# cytron_dip.net
KiCad netlist of a schematic drawn in EAGLE
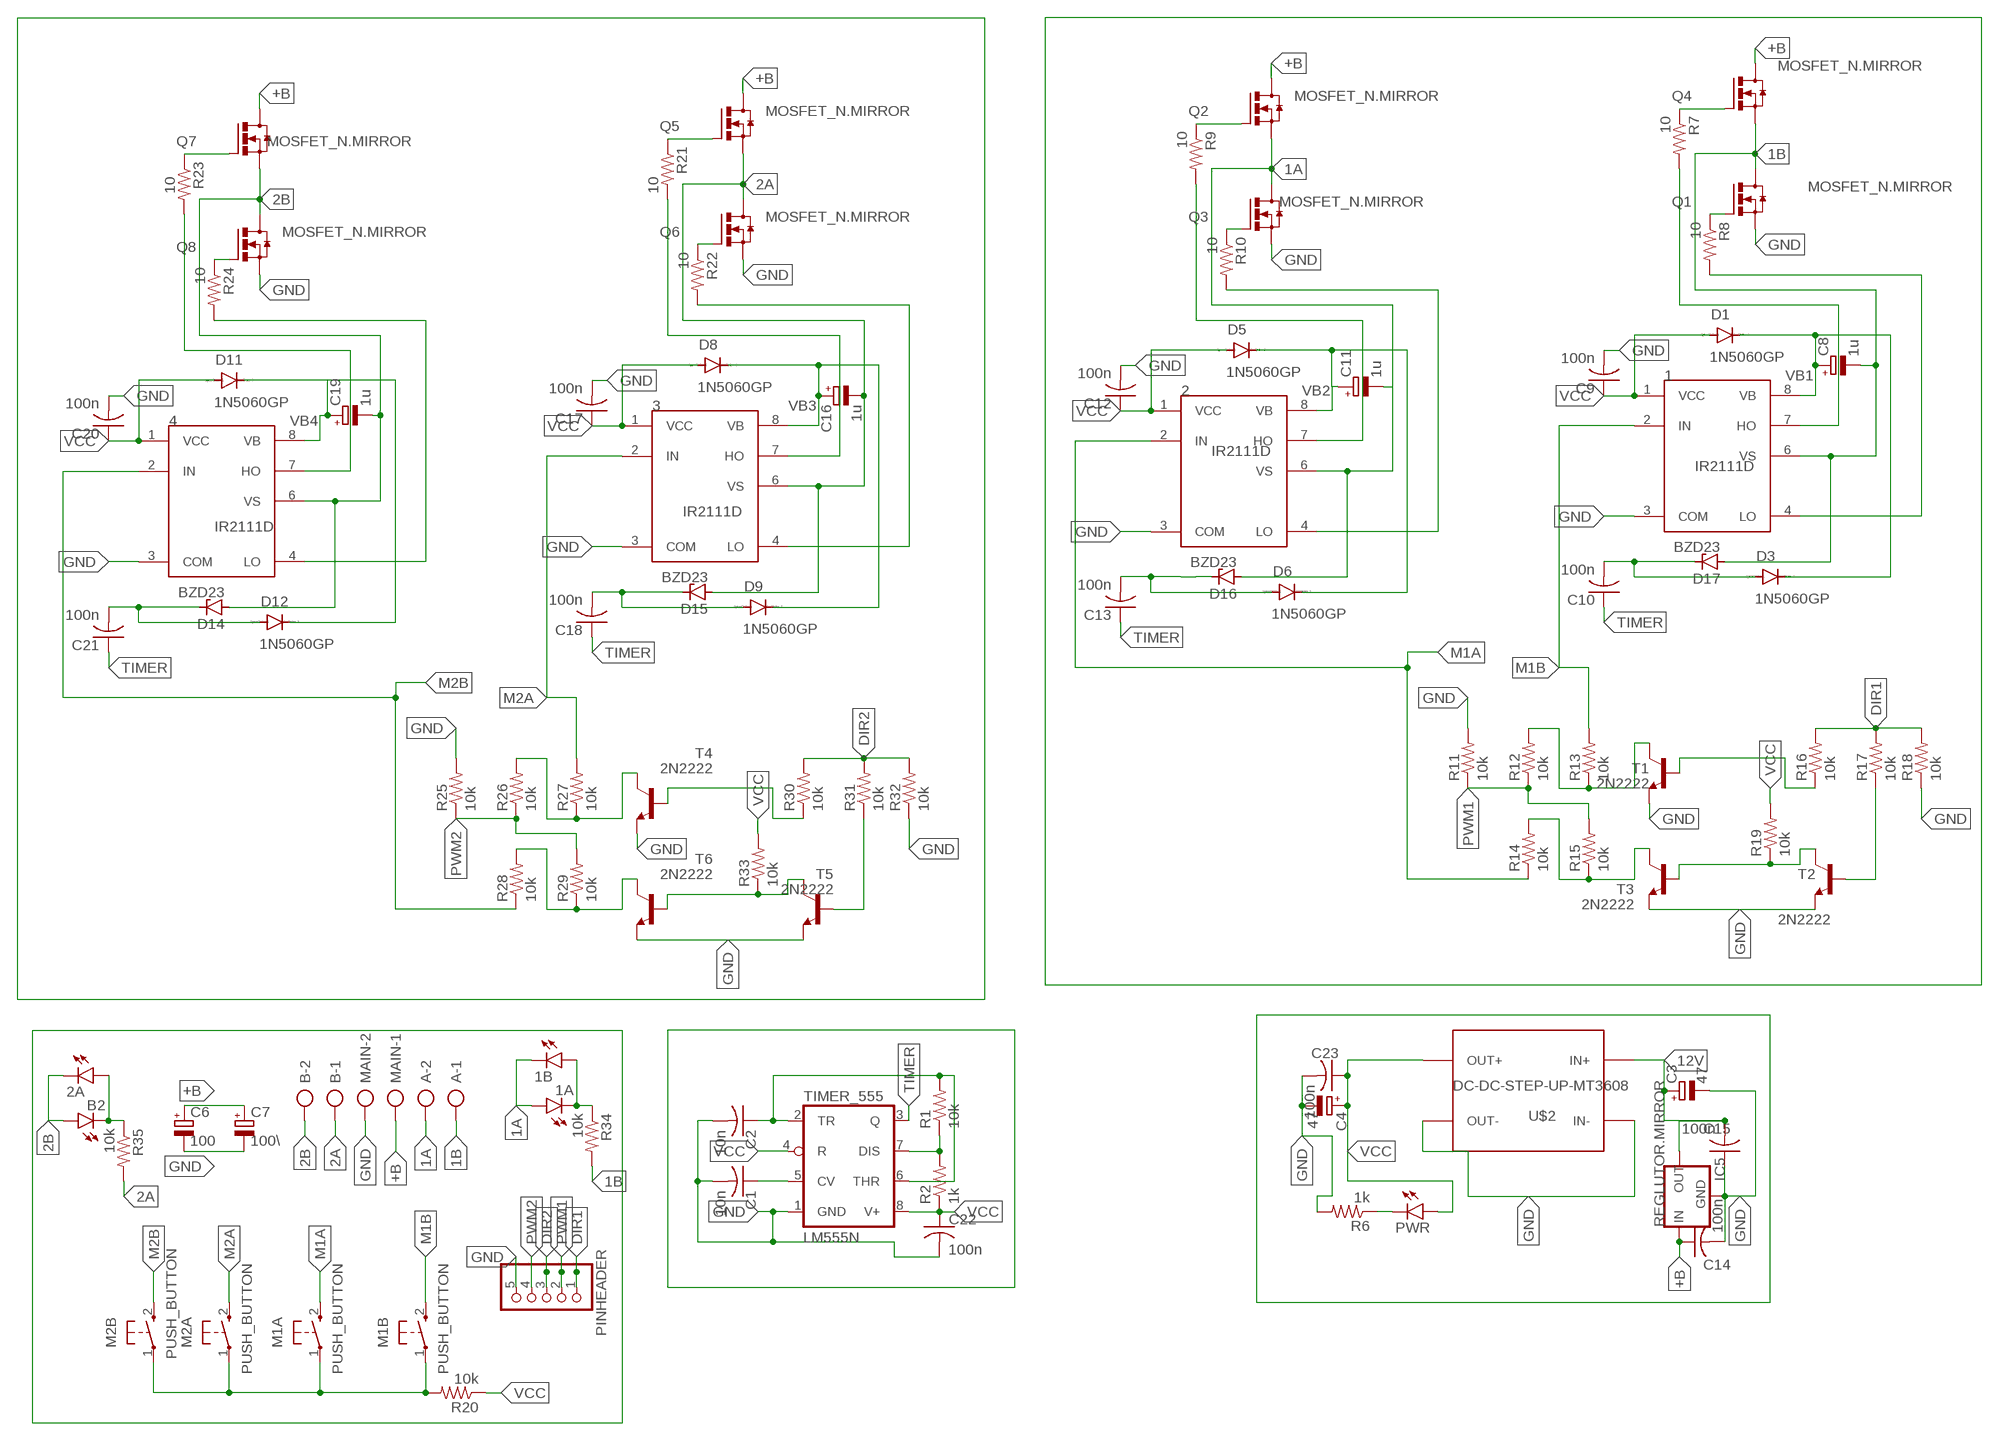
[diagram p0: schematic, sheet 1]

(export (version "E")
  (design (tool "Eeschema 10.0.6"))
  (components
    (comp (ref "1")
      (value "IR2111D")
      (footprint "eagle-import:DIL08")
      (libsource (lib "eagle-import") (part "IR2111D"))
    )
    (comp (ref "1A")
      (value "LED3MM")
      (footprint "eagle-import:LED3MM")
      (libsource (lib "eagle-import") (part "LED3MM"))
    )
    (comp (ref "1B")
      (value "LED3MM")
      (footprint "eagle-import:LED3MM")
      (libsource (lib "eagle-import") (part "LED3MM"))
    )
    (comp (ref "2")
      (value "IR2111D")
      (footprint "eagle-import:DIL08")
      (libsource (lib "eagle-import") (part "IR2111D"))
    )
    (comp (ref "2A")
      (value "LED3MM")
      (footprint "eagle-import:LED3MM")
      (libsource (lib "eagle-import") (part "LED3MM"))
    )
    (comp (ref "3")
      (value "IR2111D")
      (footprint "eagle-import:DIL08")
      (libsource (lib "eagle-import") (part "IR2111D"))
    )
    (comp (ref "4")
      (value "IR2111D")
      (footprint "eagle-import:DIL08")
      (libsource (lib "eagle-import") (part "IR2111D"))
    )
    (comp (ref "A")
      (value "AK300/22")
      (footprint "eagle-import:XTALRR488W60L1090T465H350B")
      (libsource (lib "eagle-import") (part "AK300/22"))
    )
    (comp (ref "B")
      (value "AK300/22")
      (footprint "eagle-import:XTALRR488W60L1090T465H350B")
      (libsource (lib "eagle-import") (part "AK300/22"))
    )
    (comp (ref "B2")
      (value "LED3MM")
      (footprint "eagle-import:LED3MM")
      (libsource (lib "eagle-import") (part "LED3MM"))
    )
    (comp (ref "C1")
      (value "10n")
      (footprint "eagle-import:C025-025X050")
      (libsource (lib "eagle-import") (part "C-US025-025X050"))
    )
    (comp (ref "C2")
      (value "10n")
      (footprint "eagle-import:C025-025X050")
      (libsource (lib "eagle-import") (part "C-US025-025X050"))
    )
    (comp (ref "C3")
      (value "47")
      (footprint "eagle-import:E5-10,5")
      (libsource (lib "eagle-import") (part "CPOL-EUE5-10.5"))
    )
    (comp (ref "C4")
      (value "47")
      (footprint "eagle-import:E5-10,5")
      (libsource (lib "eagle-import") (part "CPOL-EUE5-10.5"))
    )
    (comp (ref "C6")
      (value "100")
      (footprint "eagle-import:E5-10,5")
      (libsource (lib "eagle-import") (part "CPOL-EUE5-10.5"))
    )
    (comp (ref "C7")
      (value "100\\")
      (footprint "eagle-import:E5-10,5")
      (libsource (lib "eagle-import") (part "CPOL-EUE5-10.5"))
    )
    (comp (ref "C8")
      (value "1u")
      (footprint "eagle-import:E5-5")
      (libsource (lib "eagle-import") (part "CPOL-EUE5-5"))
    )
    (comp (ref "C9")
      (value "100n")
      (footprint "eagle-import:C025-025X050")
      (libsource (lib "eagle-import") (part "C-US025-025X050"))
    )
    (comp (ref "C10")
      (value "100n")
      (footprint "eagle-import:C025-025X050")
      (libsource (lib "eagle-import") (part "C-US025-025X050"))
    )
    (comp (ref "C11")
      (value "1u")
      (footprint "eagle-import:E5-5")
      (libsource (lib "eagle-import") (part "CPOL-EUE5-5"))
    )
    (comp (ref "C12")
      (value "100n")
      (footprint "eagle-import:C025-025X050")
      (libsource (lib "eagle-import") (part "C-US025-025X050"))
    )
    (comp (ref "C13")
      (value "100n")
      (footprint "eagle-import:C025-025X050")
      (libsource (lib "eagle-import") (part "C-US025-025X050"))
    )
    (comp (ref "C14")
      (value "100n")
      (footprint "eagle-import:C025-025X050")
      (libsource (lib "eagle-import") (part "C-US025-025X050"))
    )
    (comp (ref "C15")
      (value "100n")
      (footprint "eagle-import:C025-025X050")
      (libsource (lib "eagle-import") (part "C-US025-025X050"))
    )
    (comp (ref "C16")
      (value "1u")
      (footprint "eagle-import:E5-5")
      (libsource (lib "eagle-import") (part "CPOL-EUE5-5"))
    )
    (comp (ref "C17")
      (value "100n")
      (footprint "eagle-import:C025-025X050")
      (libsource (lib "eagle-import") (part "C-US025-025X050"))
    )
    (comp (ref "C18")
      (value "100n")
      (footprint "eagle-import:C025-025X050")
      (libsource (lib "eagle-import") (part "C-US025-025X050"))
    )
    (comp (ref "C19")
      (value "1u")
      (footprint "eagle-import:E5-5")
      (libsource (lib "eagle-import") (part "CPOL-EUE5-5"))
    )
    (comp (ref "C20")
      (value "100n")
      (footprint "eagle-import:C025-025X050")
      (libsource (lib "eagle-import") (part "C-US025-025X050"))
    )
    (comp (ref "C21")
      (value "100n")
      (footprint "eagle-import:C025-025X050")
      (libsource (lib "eagle-import") (part "C-US025-025X050"))
    )
    (comp (ref "C22")
      (value "100n")
      (footprint "eagle-import:C025-025X050")
      (libsource (lib "eagle-import") (part "C-US025-025X050"))
    )
    (comp (ref "C23")
      (value "100n")
      (footprint "eagle-import:C025-025X050")
      (libsource (lib "eagle-import") (part "C-US025-025X050"))
    )
    (comp (ref "D1")
      (value "1N5060GP")
      (footprint "eagle-import:DO15-12")
      (libsource (lib "eagle-import") (part "1N5060GP"))
    )
    (comp (ref "D3")
      (value "1N5060GP")
      (footprint "eagle-import:DO15-12")
      (libsource (lib "eagle-import") (part "1N5060GP"))
    )
    (comp (ref "D5")
      (value "1N5060GP")
      (footprint "eagle-import:DO15-12")
      (libsource (lib "eagle-import") (part "1N5060GP"))
    )
    (comp (ref "D6")
      (value "1N5060GP")
      (footprint "eagle-import:DO15-12")
      (libsource (lib "eagle-import") (part "1N5060GP"))
    )
    (comp (ref "D8")
      (value "1N5060GP")
      (footprint "eagle-import:DO15-12")
      (libsource (lib "eagle-import") (part "1N5060GP"))
    )
    (comp (ref "D9")
      (value "1N5060GP")
      (footprint "eagle-import:DO15-12")
      (libsource (lib "eagle-import") (part "1N5060GP"))
    )
    (comp (ref "D11")
      (value "1N5060GP")
      (footprint "eagle-import:DO15-12")
      (libsource (lib "eagle-import") (part "1N5060GP"))
    )
    (comp (ref "D12")
      (value "1N5060GP")
      (footprint "eagle-import:DO15-12")
      (libsource (lib "eagle-import") (part "1N5060GP"))
    )
    (comp (ref "D14")
      (value "BZD23")
      (footprint "eagle-import:SOD81")
      (libsource (lib "eagle-import") (part "BZD23"))
    )
    (comp (ref "D15")
      (value "BZD23")
      (footprint "eagle-import:SOD81")
      (libsource (lib "eagle-import") (part "BZD23"))
    )
    (comp (ref "D16")
      (value "BZD23")
      (footprint "eagle-import:SOD81")
      (libsource (lib "eagle-import") (part "BZD23"))
    )
    (comp (ref "D17")
      (value "BZD23")
      (footprint "eagle-import:SOD81")
      (libsource (lib "eagle-import") (part "BZD23"))
    )
    (comp (ref "IC5")
      (value "REGLUTOR.MIRROR")
      (footprint "eagle-import:78XXL.MIRROR")
      (libsource (lib "eagle-import") (part "REGLUTOR.MIRROR"))
    )
    (comp (ref "M1A")
      (value "PUSH_BUTTON")
      (footprint "eagle-import:B3F-10XX")
      (libsource (lib "eagle-import") (part "PUSH_BUTTON"))
    )
    (comp (ref "M1B")
      (value "PUSH_BUTTON")
      (footprint "eagle-import:B3F-10XX")
      (libsource (lib "eagle-import") (part "PUSH_BUTTON"))
    )
    (comp (ref "M2A")
      (value "PUSH_BUTTON")
      (footprint "eagle-import:B3F-10XX")
      (libsource (lib "eagle-import") (part "PUSH_BUTTON"))
    )
    (comp (ref "M2B")
      (value "PUSH_BUTTON")
      (footprint "eagle-import:B3F-10XX")
      (libsource (lib "eagle-import") (part "PUSH_BUTTON"))
    )
    (comp (ref "MAIN")
      (value "AK300/22")
      (footprint "eagle-import:XTALRR488W60L1090T465H350B")
      (libsource (lib "eagle-import") (part "AK300/22"))
    )
    (comp (ref "PINHEADER")
      (value "PINHD-1X5")
      (footprint "eagle-import:1X05")
      (libsource (lib "eagle-import") (part "PINHD-1X5"))
    )
    (comp (ref "PWR")
      (value "LED5MM")
      (footprint "eagle-import:LED5MM")
      (libsource (lib "eagle-import") (part "LED5MM"))
    )
    (comp (ref "Q1")
      (value "MOSFET_N.MIRROR")
      (footprint "eagle-import:TO220.MIRROR")
      (libsource (lib "eagle-import") (part "MOSFET_N.MIRROR"))
    )
    (comp (ref "Q2")
      (value "MOSFET_N.MIRROR")
      (footprint "eagle-import:TO220.MIRROR")
      (libsource (lib "eagle-import") (part "MOSFET_N.MIRROR"))
    )
    (comp (ref "Q3")
      (value "MOSFET_N.MIRROR")
      (footprint "eagle-import:TO220.MIRROR")
      (libsource (lib "eagle-import") (part "MOSFET_N.MIRROR"))
    )
    (comp (ref "Q4")
      (value "MOSFET_N.MIRROR")
      (footprint "eagle-import:TO220.MIRROR")
      (libsource (lib "eagle-import") (part "MOSFET_N.MIRROR"))
    )
    (comp (ref "Q5")
      (value "MOSFET_N.MIRROR")
      (footprint "eagle-import:TO220.MIRROR")
      (libsource (lib "eagle-import") (part "MOSFET_N.MIRROR"))
    )
    (comp (ref "Q6")
      (value "MOSFET_N.MIRROR")
      (footprint "eagle-import:TO220.MIRROR")
      (libsource (lib "eagle-import") (part "MOSFET_N.MIRROR"))
    )
    (comp (ref "Q7")
      (value "MOSFET_N.MIRROR")
      (footprint "eagle-import:TO220.MIRROR")
      (libsource (lib "eagle-import") (part "MOSFET_N.MIRROR"))
    )
    (comp (ref "Q8")
      (value "MOSFET_N.MIRROR")
      (footprint "eagle-import:TO220.MIRROR")
      (libsource (lib "eagle-import") (part "MOSFET_N.MIRROR"))
    )
    (comp (ref "R1")
      (value "10k")
      (footprint "eagle-import:0204_7")
      (libsource (lib "eagle-import") (part "R-US_0204/7"))
    )
    (comp (ref "R2")
      (value "1k")
      (footprint "eagle-import:0204_7")
      (libsource (lib "eagle-import") (part "R-US_0204/7"))
    )
    (comp (ref "R6")
      (value "1k")
      (footprint "eagle-import:0204_7")
      (libsource (lib "eagle-import") (part "R-US_0204/7"))
    )
    (comp (ref "R7")
      (value "10")
      (footprint "eagle-import:0204_7")
      (libsource (lib "eagle-import") (part "R-US_0204/7"))
    )
    (comp (ref "R8")
      (value "10")
      (footprint "eagle-import:0204_7")
      (libsource (lib "eagle-import") (part "R-US_0204/7"))
    )
    (comp (ref "R9")
      (value "10")
      (footprint "eagle-import:0204_7")
      (libsource (lib "eagle-import") (part "R-US_0204/7"))
    )
    (comp (ref "R10")
      (value "10")
      (footprint "eagle-import:0204_7")
      (libsource (lib "eagle-import") (part "R-US_0204/7"))
    )
    (comp (ref "R11")
      (value "10k")
      (footprint "eagle-import:0204_7")
      (libsource (lib "eagle-import") (part "R-US_0204/7"))
    )
    (comp (ref "R12")
      (value "10k")
      (footprint "eagle-import:0204_7")
      (libsource (lib "eagle-import") (part "R-US_0204/7"))
    )
    (comp (ref "R13")
      (value "10k")
      (footprint "eagle-import:0204_7")
      (libsource (lib "eagle-import") (part "R-US_0204/7"))
    )
    (comp (ref "R14")
      (value "10k")
      (footprint "eagle-import:0204_7")
      (libsource (lib "eagle-import") (part "R-US_0204/7"))
    )
    (comp (ref "R15")
      (value "10k")
      (footprint "eagle-import:0204_7")
      (libsource (lib "eagle-import") (part "R-US_0204/7"))
    )
    (comp (ref "R16")
      (value "10k")
      (footprint "eagle-import:0204_7")
      (libsource (lib "eagle-import") (part "R-US_0204/7"))
    )
    (comp (ref "R17")
      (value "10k")
      (footprint "eagle-import:0204_7")
      (libsource (lib "eagle-import") (part "R-US_0204/7"))
    )
    (comp (ref "R18")
      (value "10k")
      (footprint "eagle-import:0204_7")
      (libsource (lib "eagle-import") (part "R-US_0204/7"))
    )
    (comp (ref "R19")
      (value "10k")
      (footprint "eagle-import:0204_7")
      (libsource (lib "eagle-import") (part "R-US_0204/7"))
    )
    (comp (ref "R20")
      (value "10k")
      (footprint "eagle-import:0204_7")
      (libsource (lib "eagle-import") (part "R-US_0204/7"))
    )
    (comp (ref "R21")
      (value "10")
      (footprint "eagle-import:0204_7")
      (libsource (lib "eagle-import") (part "R-US_0204/7"))
    )
    (comp (ref "R22")
      (value "10")
      (footprint "eagle-import:0204_7")
      (libsource (lib "eagle-import") (part "R-US_0204/7"))
    )
    (comp (ref "R23")
      (value "10")
      (footprint "eagle-import:0204_7")
      (libsource (lib "eagle-import") (part "R-US_0204/7"))
    )
    (comp (ref "R24")
      (value "10")
      (footprint "eagle-import:0204_7")
      (libsource (lib "eagle-import") (part "R-US_0204/7"))
    )
    (comp (ref "R25")
      (value "10k")
      (footprint "eagle-import:0204_7")
      (libsource (lib "eagle-import") (part "R-US_0204/7"))
    )
    (comp (ref "R26")
      (value "10k")
      (footprint "eagle-import:0204_7")
      (libsource (lib "eagle-import") (part "R-US_0204/7"))
    )
    (comp (ref "R27")
      (value "10k")
      (footprint "eagle-import:0204_7")
      (libsource (lib "eagle-import") (part "R-US_0204/7"))
    )
    (comp (ref "R28")
      (value "10k")
      (footprint "eagle-import:0204_7")
      (libsource (lib "eagle-import") (part "R-US_0204/7"))
    )
    (comp (ref "R29")
      (value "10k")
      (footprint "eagle-import:0204_7")
      (libsource (lib "eagle-import") (part "R-US_0204/7"))
    )
    (comp (ref "R30")
      (value "10k")
      (footprint "eagle-import:0204_7")
      (libsource (lib "eagle-import") (part "R-US_0204/7"))
    )
    (comp (ref "R31")
      (value "10k")
      (footprint "eagle-import:0204_7")
      (libsource (lib "eagle-import") (part "R-US_0204/7"))
    )
    (comp (ref "R32")
      (value "10k")
      (footprint "eagle-import:0204_7")
      (libsource (lib "eagle-import") (part "R-US_0204/7"))
    )
    (comp (ref "R33")
      (value "10k")
      (footprint "eagle-import:0204_7")
      (libsource (lib "eagle-import") (part "R-US_0204/7"))
    )
    (comp (ref "R34")
      (value "10k")
      (footprint "eagle-import:0204_7")
      (libsource (lib "eagle-import") (part "R-US_0204/7"))
    )
    (comp (ref "R35")
      (value "10k")
      (footprint "eagle-import:0204_7")
      (libsource (lib "eagle-import") (part "R-US_0204/7"))
    )
    (comp (ref "T1")
      (value "2N2222")
      (footprint "eagle-import:TO18")
      (libsource (lib "eagle-import") (part "2N2222"))
    )
    (comp (ref "T2")
      (value "2N2222")
      (footprint "eagle-import:TO18")
      (libsource (lib "eagle-import") (part "2N2222"))
    )
    (comp (ref "T3")
      (value "2N2222")
      (footprint "eagle-import:TO18")
      (libsource (lib "eagle-import") (part "2N2222"))
    )
    (comp (ref "T4")
      (value "2N2222")
      (footprint "eagle-import:TO18")
      (libsource (lib "eagle-import") (part "2N2222"))
    )
    (comp (ref "T5")
      (value "2N2222")
      (footprint "eagle-import:TO18")
      (libsource (lib "eagle-import") (part "2N2222"))
    )
    (comp (ref "T6")
      (value "2N2222")
      (footprint "eagle-import:TO18")
      (libsource (lib "eagle-import") (part "2N2222"))
    )
    (comp (ref "TIMER_555")
      (value "LM555N")
      (footprint "eagle-import:DIL08")
      (libsource (lib "eagle-import") (part "555NLM"))
    )
    (comp (ref "U$2")
      (value "DC-DC-STEP-UP-MT3608")
      (footprint "eagle-import:DC-DC-STEP-UP-MT3608")
      (libsource (lib "eagle-import") (part "DC-DC-STEP-UP-MT3608"))
    )
  )
  (nets
    (net (code "1") (name "+B") (class "Default")
      (node (ref "C14") (pin "1") (pinfunction "1_1") (pintype "passive"))
      (node (ref "C6") (pin "+") (pinfunction "+_+") (pintype "passive"))
      (node (ref "C7") (pin "+") (pinfunction "+_+") (pintype "passive"))
      (node (ref "IC5") (pin "IN") (pinfunction "IN_IN") (pintype "input"))
      (node (ref "MAIN") (pin "1") (pinfunction "KL_1") (pintype "passive"))
      (node (ref "Q2") (pin "D") (pinfunction "D_D") (pintype "passive"))
      (node (ref "Q4") (pin "D") (pinfunction "D_D") (pintype "passive"))
      (node (ref "Q5") (pin "D") (pinfunction "D_D") (pintype "passive"))
      (node (ref "Q7") (pin "D") (pinfunction "D_D") (pintype "passive"))
    )
    (net (code "2") (name "/VB1") (class "Default")
      (node (ref "1") (pin "8") (pinfunction "VB_8") (pintype "power_in"))
      (node (ref "C8") (pin "+") (pinfunction "+_+") (pintype "passive"))
      (node (ref "D1") (pin "C") (pinfunction "C_C") (pintype "passive"))
      (node (ref "D3") (pin "C") (pinfunction "C_C") (pintype "passive"))
    )
    (net (code "3") (name "/VB2") (class "Default")
      (node (ref "2") (pin "8") (pinfunction "VB_8") (pintype "power_in"))
      (node (ref "C11") (pin "+") (pinfunction "+_+") (pintype "passive"))
      (node (ref "D5") (pin "C") (pinfunction "C_C") (pintype "passive"))
      (node (ref "D6") (pin "C") (pinfunction "C_C") (pintype "passive"))
    )
    (net (code "4") (name "/VB3") (class "Default")
      (node (ref "3") (pin "8") (pinfunction "VB_8") (pintype "power_in"))
      (node (ref "C16") (pin "+") (pinfunction "+_+") (pintype "passive"))
      (node (ref "D8") (pin "C") (pinfunction "C_C") (pintype "passive"))
      (node (ref "D9") (pin "C") (pinfunction "C_C") (pintype "passive"))
    )
    (net (code "5") (name "/VB4") (class "Default")
      (node (ref "4") (pin "8") (pinfunction "VB_8") (pintype "power_in"))
      (node (ref "C19") (pin "+") (pinfunction "+_+") (pintype "passive"))
      (node (ref "D11") (pin "C") (pinfunction "C_C") (pintype "passive"))
      (node (ref "D12") (pin "C") (pinfunction "C_C") (pintype "passive"))
    )
    (net (code "6") (name "1A") (class "Default")
      (node (ref "1A") (pin "A") (pinfunction "A_A") (pintype "passive"))
      (node (ref "1B") (pin "K") (pinfunction "C_K") (pintype "passive"))
      (node (ref "2") (pin "6") (pinfunction "VS_6") (pintype "power_in"))
      (node (ref "A") (pin "2") (pinfunction "KL_2") (pintype "passive"))
      (node (ref "C11") (pin "-") (pinfunction "-_-") (pintype "passive"))
      (node (ref "D16") (pin "A") (pinfunction "A_A") (pintype "passive"))
      (node (ref "Q2") (pin "S") (pinfunction "S_S") (pintype "passive"))
      (node (ref "Q3") (pin "D") (pinfunction "D_D") (pintype "passive"))
    )
    (net (code "7") (name "1B") (class "Default")
      (node (ref "1") (pin "6") (pinfunction "VS_6") (pintype "power_in"))
      (node (ref "A") (pin "1") (pinfunction "KL_1") (pintype "passive"))
      (node (ref "C8") (pin "-") (pinfunction "-_-") (pintype "passive"))
      (node (ref "D17") (pin "A") (pinfunction "A_A") (pintype "passive"))
      (node (ref "Q1") (pin "D") (pinfunction "D_D") (pintype "passive"))
      (node (ref "Q4") (pin "S") (pinfunction "S_S") (pintype "passive"))
      (node (ref "R34") (pin "2") (pinfunction "2_2") (pintype "passive"))
    )
    (net (code "8") (name "2A") (class "Default")
      (node (ref "3") (pin "6") (pinfunction "VS_6") (pintype "power_in"))
      (node (ref "B") (pin "1") (pinfunction "KL_1") (pintype "passive"))
      (node (ref "C16") (pin "-") (pinfunction "-_-") (pintype "passive"))
      (node (ref "D15") (pin "A") (pinfunction "A_A") (pintype "passive"))
      (node (ref "Q5") (pin "S") (pinfunction "S_S") (pintype "passive"))
      (node (ref "Q6") (pin "D") (pinfunction "D_D") (pintype "passive"))
      (node (ref "R35") (pin "2") (pinfunction "2_2") (pintype "passive"))
    )
    (net (code "9") (name "2B") (class "Default")
      (node (ref "2A") (pin "K") (pinfunction "C_K") (pintype "passive"))
      (node (ref "4") (pin "6") (pinfunction "VS_6") (pintype "power_in"))
      (node (ref "B") (pin "2") (pinfunction "KL_2") (pintype "passive"))
      (node (ref "B2") (pin "A") (pinfunction "A_A") (pintype "passive"))
      (node (ref "C19") (pin "-") (pinfunction "-_-") (pintype "passive"))
      (node (ref "D14") (pin "A") (pinfunction "A_A") (pintype "passive"))
      (node (ref "Q7") (pin "S") (pinfunction "S_S") (pintype "passive"))
      (node (ref "Q8") (pin "D") (pinfunction "D_D") (pintype "passive"))
    )
    (net (code "10") (name "12V") (class "Default")
      (node (ref "C15") (pin "2") (pinfunction "2_2") (pintype "passive"))
      (node (ref "C3") (pin "+") (pinfunction "+_+") (pintype "passive"))
      (node (ref "IC5") (pin "OUT") (pinfunction "OUT_OUT") (pintype "passive"))
      (node (ref "U$2") (pin "IN+") (pinfunction "IN+_IN+") (pintype "bidirectional"))
    )
    (net (code "11") (name "DIR1") (class "Default")
      (node (ref "PINHEADER") (pin "1") (pinfunction "1_1") (pintype "passive"))
      (node (ref "R16") (pin "2") (pinfunction "2_2") (pintype "passive"))
      (node (ref "R17") (pin "2") (pinfunction "2_2") (pintype "passive"))
      (node (ref "R18") (pin "2") (pinfunction "2_2") (pintype "passive"))
    )
    (net (code "12") (name "DIR2") (class "Default")
      (node (ref "PINHEADER") (pin "3") (pinfunction "3_3") (pintype "passive"))
      (node (ref "R30") (pin "2") (pinfunction "2_2") (pintype "passive"))
      (node (ref "R31") (pin "2") (pinfunction "2_2") (pintype "passive"))
      (node (ref "R32") (pin "2") (pinfunction "2_2") (pintype "passive"))
    )
    (net (code "13") (name "GND") (class "Default")
      (node (ref "1") (pin "3") (pinfunction "COM_3") (pintype "power_in"))
      (node (ref "2") (pin "3") (pinfunction "COM_3") (pintype "power_in"))
      (node (ref "3") (pin "3") (pinfunction "COM_3") (pintype "power_in"))
      (node (ref "4") (pin "3") (pinfunction "COM_3") (pintype "power_in"))
      (node (ref "C1") (pin "2") (pinfunction "2_2") (pintype "passive"))
      (node (ref "C12") (pin "2") (pinfunction "2_2") (pintype "passive"))
      (node (ref "C14") (pin "2") (pinfunction "2_2") (pintype "passive"))
      (node (ref "C15") (pin "1") (pinfunction "1_1") (pintype "passive"))
      (node (ref "C17") (pin "2") (pinfunction "2_2") (pintype "passive"))
      (node (ref "C2") (pin "2") (pinfunction "2_2") (pintype "passive"))
      (node (ref "C20") (pin "2") (pinfunction "2_2") (pintype "passive"))
      (node (ref "C22") (pin "2") (pinfunction "2_2") (pintype "passive"))
      (node (ref "C23") (pin "2") (pinfunction "2_2") (pintype "passive"))
      (node (ref "C3") (pin "-") (pinfunction "-_-") (pintype "passive"))
      (node (ref "C4") (pin "-") (pinfunction "-_-") (pintype "passive"))
      (node (ref "C6") (pin "-") (pinfunction "-_-") (pintype "passive"))
      (node (ref "C7") (pin "-") (pinfunction "-_-") (pintype "passive"))
      (node (ref "C9") (pin "2") (pinfunction "2_2") (pintype "passive"))
      (node (ref "IC5") (pin "GND") (pinfunction "GND_GND") (pintype "input"))
      (node (ref "MAIN") (pin "2") (pinfunction "KL_2") (pintype "passive"))
      (node (ref "PINHEADER") (pin "5") (pinfunction "5_5") (pintype "passive"))
      (node (ref "Q1") (pin "S") (pinfunction "S_S") (pintype "passive"))
      (node (ref "Q3") (pin "S") (pinfunction "S_S") (pintype "passive"))
      (node (ref "Q6") (pin "S") (pinfunction "S_S") (pintype "passive"))
      (node (ref "Q8") (pin "S") (pinfunction "S_S") (pintype "passive"))
      (node (ref "R11") (pin "2") (pinfunction "2_2") (pintype "passive"))
      (node (ref "R18") (pin "1") (pinfunction "1_1") (pintype "passive"))
      (node (ref "R25") (pin "2") (pinfunction "2_2") (pintype "passive"))
      (node (ref "R32") (pin "1") (pinfunction "1_1") (pintype "passive"))
      (node (ref "R6") (pin "2") (pinfunction "2_2") (pintype "passive"))
      (node (ref "T1") (pin "1") (pinfunction "E_1") (pintype "passive"))
      (node (ref "T2") (pin "1") (pinfunction "E_1") (pintype "passive"))
      (node (ref "T3") (pin "1") (pinfunction "E_1") (pintype "passive"))
      (node (ref "T4") (pin "1") (pinfunction "E_1") (pintype "passive"))
      (node (ref "T5") (pin "1") (pinfunction "E_1") (pintype "passive"))
      (node (ref "T6") (pin "1") (pinfunction "E_1") (pintype "passive"))
      (node (ref "TIMER_555") (pin "1") (pinfunction "GND_1") (pintype "power_in"))
      (node (ref "U$2") (pin "IN-") (pinfunction "IN-_IN-") (pintype "bidirectional"))
      (node (ref "U$2") (pin "OUT-") (pinfunction "OUT-_OUT-") (pintype "bidirectional"))
    )
    (net (code "14") (name "M1A") (class "Default")
      (node (ref "2") (pin "2") (pinfunction "IN_2") (pintype "input"))
      (node (ref "M1A") (pin "2") (pinfunction "S_2") (pintype "passive"))
      (node (ref "R14") (pin "1") (pinfunction "1_1") (pintype "passive"))
    )
    (net (code "15") (name "M1B") (class "Default")
      (node (ref "1") (pin "2") (pinfunction "IN_2") (pintype "input"))
      (node (ref "M1B") (pin "2") (pinfunction "S_2") (pintype "passive"))
      (node (ref "R13") (pin "2") (pinfunction "2_2") (pintype "passive"))
    )
    (net (code "16") (name "M2A") (class "Default")
      (node (ref "3") (pin "2") (pinfunction "IN_2") (pintype "input"))
      (node (ref "M2A") (pin "2") (pinfunction "S_2") (pintype "passive"))
      (node (ref "R27") (pin "2") (pinfunction "2_2") (pintype "passive"))
    )
    (net (code "17") (name "M2B") (class "Default")
      (node (ref "4") (pin "2") (pinfunction "IN_2") (pintype "input"))
      (node (ref "M2B") (pin "2") (pinfunction "S_2") (pintype "passive"))
      (node (ref "R28") (pin "1") (pinfunction "1_1") (pintype "passive"))
    )
    (net (code "18") (name "Net-(1-HO)") (class "Default")
      (node (ref "1") (pin "7") (pinfunction "HO_7") (pintype "output"))
      (node (ref "R7") (pin "2") (pinfunction "2_2") (pintype "passive"))
    )
    (net (code "19") (name "Net-(1-LO)") (class "Default")
      (node (ref "1") (pin "4") (pinfunction "LO_4") (pintype "output"))
      (node (ref "R8") (pin "2") (pinfunction "2_2") (pintype "passive"))
    )
    (net (code "20") (name "Net-(1A-C)") (class "Default")
      (node (ref "1A") (pin "K") (pinfunction "C_K") (pintype "passive"))
      (node (ref "1B") (pin "A") (pinfunction "A_A") (pintype "passive"))
      (node (ref "R34") (pin "1") (pinfunction "1_1") (pintype "passive"))
    )
    (net (code "21") (name "Net-(2-HO)") (class "Default")
      (node (ref "2") (pin "7") (pinfunction "HO_7") (pintype "output"))
      (node (ref "R9") (pin "2") (pinfunction "2_2") (pintype "passive"))
    )
    (net (code "22") (name "Net-(2-LO)") (class "Default")
      (node (ref "2") (pin "4") (pinfunction "LO_4") (pintype "output"))
      (node (ref "R10") (pin "2") (pinfunction "2_2") (pintype "passive"))
    )
    (net (code "23") (name "Net-(3-HO)") (class "Default")
      (node (ref "3") (pin "7") (pinfunction "HO_7") (pintype "output"))
      (node (ref "R21") (pin "2") (pinfunction "2_2") (pintype "passive"))
    )
    (net (code "24") (name "Net-(3-LO)") (class "Default")
      (node (ref "3") (pin "4") (pinfunction "LO_4") (pintype "output"))
      (node (ref "R22") (pin "2") (pinfunction "2_2") (pintype "passive"))
    )
    (net (code "25") (name "Net-(4-HO)") (class "Default")
      (node (ref "4") (pin "7") (pinfunction "HO_7") (pintype "output"))
      (node (ref "R23") (pin "2") (pinfunction "2_2") (pintype "passive"))
    )
    (net (code "26") (name "Net-(4-LO)") (class "Default")
      (node (ref "4") (pin "4") (pinfunction "LO_4") (pintype "output"))
      (node (ref "R24") (pin "2") (pinfunction "2_2") (pintype "passive"))
    )
    (net (code "27") (name "Net-(B2-C)") (class "Default")
      (node (ref "2A") (pin "A") (pinfunction "A_A") (pintype "passive"))
      (node (ref "B2") (pin "K") (pinfunction "C_K") (pintype "passive"))
      (node (ref "R35") (pin "1") (pinfunction "1_1") (pintype "passive"))
    )
    (net (code "28") (name "Net-(C10-Pad2)") (class "Default")
      (node (ref "C10") (pin "2") (pinfunction "2_2") (pintype "passive"))
      (node (ref "D17") (pin "C") (pinfunction "C_C") (pintype "passive"))
      (node (ref "D3") (pin "A") (pinfunction "A_A") (pintype "passive"))
    )
    (net (code "29") (name "Net-(C13-Pad2)") (class "Default")
      (node (ref "C13") (pin "2") (pinfunction "2_2") (pintype "passive"))
      (node (ref "D16") (pin "C") (pinfunction "C_C") (pintype "passive"))
      (node (ref "D6") (pin "A") (pinfunction "A_A") (pintype "passive"))
    )
    (net (code "30") (name "Net-(C18-Pad2)") (class "Default")
      (node (ref "C18") (pin "2") (pinfunction "2_2") (pintype "passive"))
      (node (ref "D15") (pin "C") (pinfunction "C_C") (pintype "passive"))
      (node (ref "D9") (pin "A") (pinfunction "A_A") (pintype "passive"))
    )
    (net (code "31") (name "Net-(C21-Pad2)") (class "Default")
      (node (ref "C21") (pin "2") (pinfunction "2_2") (pintype "passive"))
      (node (ref "D12") (pin "A") (pinfunction "A_A") (pintype "passive"))
      (node (ref "D14") (pin "C") (pinfunction "C_C") (pintype "passive"))
    )
    (net (code "32") (name "Net-(M1A-P)") (class "Default")
      (node (ref "M1A") (pin "1") (pinfunction "P_1") (pintype "passive"))
      (node (ref "M1B") (pin "1") (pinfunction "P_1") (pintype "passive"))
      (node (ref "M2A") (pin "1") (pinfunction "P_1") (pintype "passive"))
      (node (ref "M2B") (pin "1") (pinfunction "P_1") (pintype "passive"))
      (node (ref "R20") (pin "2") (pinfunction "2_2") (pintype "passive"))
    )
    (net (code "33") (name "Net-(PWR-C)") (class "Default")
      (node (ref "PWR") (pin "K") (pinfunction "C_K") (pintype "passive"))
      (node (ref "R6") (pin "1") (pinfunction "1_1") (pintype "passive"))
    )
    (net (code "34") (name "Net-(Q1-PadG)") (class "Default")
      (node (ref "Q1") (pin "G") (pinfunction "G_G") (pintype "passive"))
      (node (ref "R8") (pin "1") (pinfunction "1_1") (pintype "passive"))
    )
    (net (code "35") (name "Net-(Q2-PadG)") (class "Default")
      (node (ref "Q2") (pin "G") (pinfunction "G_G") (pintype "passive"))
      (node (ref "R9") (pin "1") (pinfunction "1_1") (pintype "passive"))
    )
    (net (code "36") (name "Net-(Q3-PadG)") (class "Default")
      (node (ref "Q3") (pin "G") (pinfunction "G_G") (pintype "passive"))
      (node (ref "R10") (pin "1") (pinfunction "1_1") (pintype "passive"))
    )
    (net (code "37") (name "Net-(Q4-PadG)") (class "Default")
      (node (ref "Q4") (pin "G") (pinfunction "G_G") (pintype "passive"))
      (node (ref "R7") (pin "1") (pinfunction "1_1") (pintype "passive"))
    )
    (net (code "38") (name "Net-(Q5-PadG)") (class "Default")
      (node (ref "Q5") (pin "G") (pinfunction "G_G") (pintype "passive"))
      (node (ref "R21") (pin "1") (pinfunction "1_1") (pintype "passive"))
    )
    (net (code "39") (name "Net-(Q6-PadG)") (class "Default")
      (node (ref "Q6") (pin "G") (pinfunction "G_G") (pintype "passive"))
      (node (ref "R22") (pin "1") (pinfunction "1_1") (pintype "passive"))
    )
    (net (code "40") (name "Net-(Q7-PadG)") (class "Default")
      (node (ref "Q7") (pin "G") (pinfunction "G_G") (pintype "passive"))
      (node (ref "R23") (pin "1") (pinfunction "1_1") (pintype "passive"))
    )
    (net (code "41") (name "Net-(Q8-PadG)") (class "Default")
      (node (ref "Q8") (pin "G") (pinfunction "G_G") (pintype "passive"))
      (node (ref "R24") (pin "1") (pinfunction "1_1") (pintype "passive"))
    )
    (net (code "42") (name "Net-(T1-B)") (class "Default")
      (node (ref "R16") (pin "1") (pinfunction "1_1") (pintype "passive"))
      (node (ref "T1") (pin "2") (pinfunction "B_2") (pintype "passive"))
    )
    (net (code "43") (name "Net-(T1-C)") (class "Default")
      (node (ref "R12") (pin "2") (pinfunction "2_2") (pintype "passive"))
      (node (ref "R13") (pin "1") (pinfunction "1_1") (pintype "passive"))
      (node (ref "T1") (pin "3") (pinfunction "C_3") (pintype "passive"))
    )
    (net (code "44") (name "Net-(T2-B)") (class "Default")
      (node (ref "R17") (pin "1") (pinfunction "1_1") (pintype "passive"))
      (node (ref "T2") (pin "2") (pinfunction "B_2") (pintype "passive"))
    )
    (net (code "45") (name "Net-(T2-C)") (class "Default")
      (node (ref "R19") (pin "1") (pinfunction "1_1") (pintype "passive"))
      (node (ref "T2") (pin "3") (pinfunction "C_3") (pintype "passive"))
      (node (ref "T3") (pin "2") (pinfunction "B_2") (pintype "passive"))
    )
    (net (code "46") (name "Net-(T3-C)") (class "Default")
      (node (ref "R14") (pin "2") (pinfunction "2_2") (pintype "passive"))
      (node (ref "R15") (pin "1") (pinfunction "1_1") (pintype "passive"))
      (node (ref "T3") (pin "3") (pinfunction "C_3") (pintype "passive"))
    )
    (net (code "47") (name "Net-(T4-B)") (class "Default")
      (node (ref "R30") (pin "1") (pinfunction "1_1") (pintype "passive"))
      (node (ref "T4") (pin "2") (pinfunction "B_2") (pintype "passive"))
    )
    (net (code "48") (name "Net-(T4-C)") (class "Default")
      (node (ref "R26") (pin "2") (pinfunction "2_2") (pintype "passive"))
      (node (ref "R27") (pin "1") (pinfunction "1_1") (pintype "passive"))
      (node (ref "T4") (pin "3") (pinfunction "C_3") (pintype "passive"))
    )
    (net (code "49") (name "Net-(T5-B)") (class "Default")
      (node (ref "R31") (pin "1") (pinfunction "1_1") (pintype "passive"))
      (node (ref "T5") (pin "2") (pinfunction "B_2") (pintype "passive"))
    )
    (net (code "50") (name "Net-(T5-C)") (class "Default")
      (node (ref "R33") (pin "1") (pinfunction "1_1") (pintype "passive"))
      (node (ref "T5") (pin "3") (pinfunction "C_3") (pintype "passive"))
      (node (ref "T6") (pin "2") (pinfunction "B_2") (pintype "passive"))
    )
    (net (code "51") (name "Net-(T6-C)") (class "Default")
      (node (ref "R28") (pin "2") (pinfunction "2_2") (pintype "passive"))
      (node (ref "R29") (pin "1") (pinfunction "1_1") (pintype "passive"))
      (node (ref "T6") (pin "3") (pinfunction "C_3") (pintype "passive"))
    )
    (net (code "52") (name "Net-(TIMER_555-CV)") (class "Default")
      (node (ref "C1") (pin "1") (pinfunction "1_1") (pintype "passive"))
      (node (ref "TIMER_555") (pin "5") (pinfunction "CV_5") (pintype "input"))
    )
    (net (code "53") (name "Net-(TIMER_555-DIS)") (class "Default")
      (node (ref "R1") (pin "1") (pinfunction "1_1") (pintype "passive"))
      (node (ref "R2") (pin "2") (pinfunction "2_2") (pintype "passive"))
      (node (ref "TIMER_555") (pin "7") (pinfunction "DIS_7") (pintype "input"))
    )
    (net (code "54") (name "Net-(TIMER_555-THR)") (class "Default")
      (node (ref "C2") (pin "1") (pinfunction "1_1") (pintype "passive"))
      (node (ref "R1") (pin "2") (pinfunction "2_2") (pintype "passive"))
      (node (ref "TIMER_555") (pin "2") (pinfunction "TR_2") (pintype "input"))
      (node (ref "TIMER_555") (pin "6") (pinfunction "THR_6") (pintype "input"))
    )
    (net (code "55") (name "PWM1") (class "Default")
      (node (ref "PINHEADER") (pin "2") (pinfunction "2_2") (pintype "passive"))
      (node (ref "R11") (pin "1") (pinfunction "1_1") (pintype "passive"))
      (node (ref "R12") (pin "1") (pinfunction "1_1") (pintype "passive"))
      (node (ref "R15") (pin "2") (pinfunction "2_2") (pintype "passive"))
    )
    (net (code "56") (name "PWM2") (class "Default")
      (node (ref "PINHEADER") (pin "4") (pinfunction "4_4") (pintype "passive"))
      (node (ref "R25") (pin "1") (pinfunction "1_1") (pintype "passive"))
      (node (ref "R26") (pin "1") (pinfunction "1_1") (pintype "passive"))
      (node (ref "R29") (pin "2") (pinfunction "2_2") (pintype "passive"))
    )
    (net (code "57") (name "TIMER") (class "Default")
      (node (ref "C10") (pin "1") (pinfunction "1_1") (pintype "passive"))
      (node (ref "C13") (pin "1") (pinfunction "1_1") (pintype "passive"))
      (node (ref "C18") (pin "1") (pinfunction "1_1") (pintype "passive"))
      (node (ref "C21") (pin "1") (pinfunction "1_1") (pintype "passive"))
      (node (ref "TIMER_555") (pin "3") (pinfunction "Q_3") (pintype "output"))
    )
    (net (code "58") (name "VCC") (class "Default")
      (node (ref "1") (pin "1") (pinfunction "VCC_1") (pintype "power_in"))
      (node (ref "2") (pin "1") (pinfunction "VCC_1") (pintype "power_in"))
      (node (ref "3") (pin "1") (pinfunction "VCC_1") (pintype "power_in"))
      (node (ref "4") (pin "1") (pinfunction "VCC_1") (pintype "power_in"))
      (node (ref "C12") (pin "1") (pinfunction "1_1") (pintype "passive"))
      (node (ref "C17") (pin "1") (pinfunction "1_1") (pintype "passive"))
      (node (ref "C20") (pin "1") (pinfunction "1_1") (pintype "passive"))
      (node (ref "C22") (pin "1") (pinfunction "1_1") (pintype "passive"))
      (node (ref "C23") (pin "1") (pinfunction "1_1") (pintype "passive"))
      (node (ref "C4") (pin "+") (pinfunction "+_+") (pintype "passive"))
      (node (ref "C9") (pin "1") (pinfunction "1_1") (pintype "passive"))
      (node (ref "D1") (pin "A") (pinfunction "A_A") (pintype "passive"))
      (node (ref "D11") (pin "A") (pinfunction "A_A") (pintype "passive"))
      (node (ref "D5") (pin "A") (pinfunction "A_A") (pintype "passive"))
      (node (ref "D8") (pin "A") (pinfunction "A_A") (pintype "passive"))
      (node (ref "PWR") (pin "A") (pinfunction "A_A") (pintype "passive"))
      (node (ref "R19") (pin "2") (pinfunction "2_2") (pintype "passive"))
      (node (ref "R2") (pin "1") (pinfunction "1_1") (pintype "passive"))
      (node (ref "R20") (pin "1") (pinfunction "1_1") (pintype "passive"))
      (node (ref "R33") (pin "2") (pinfunction "2_2") (pintype "passive"))
      (node (ref "TIMER_555") (pin "4") (pinfunction "R_4") (pintype "input"))
      (node (ref "TIMER_555") (pin "8") (pinfunction "V+_8") (pintype "power_in"))
      (node (ref "U$2") (pin "OUT+") (pinfunction "OUT+_OUT+") (pintype "bidirectional"))
    )
  )
)
